# 01-Driver_Board_Overview.net
KiCad netlist of a schematic drawn in Altium Designer
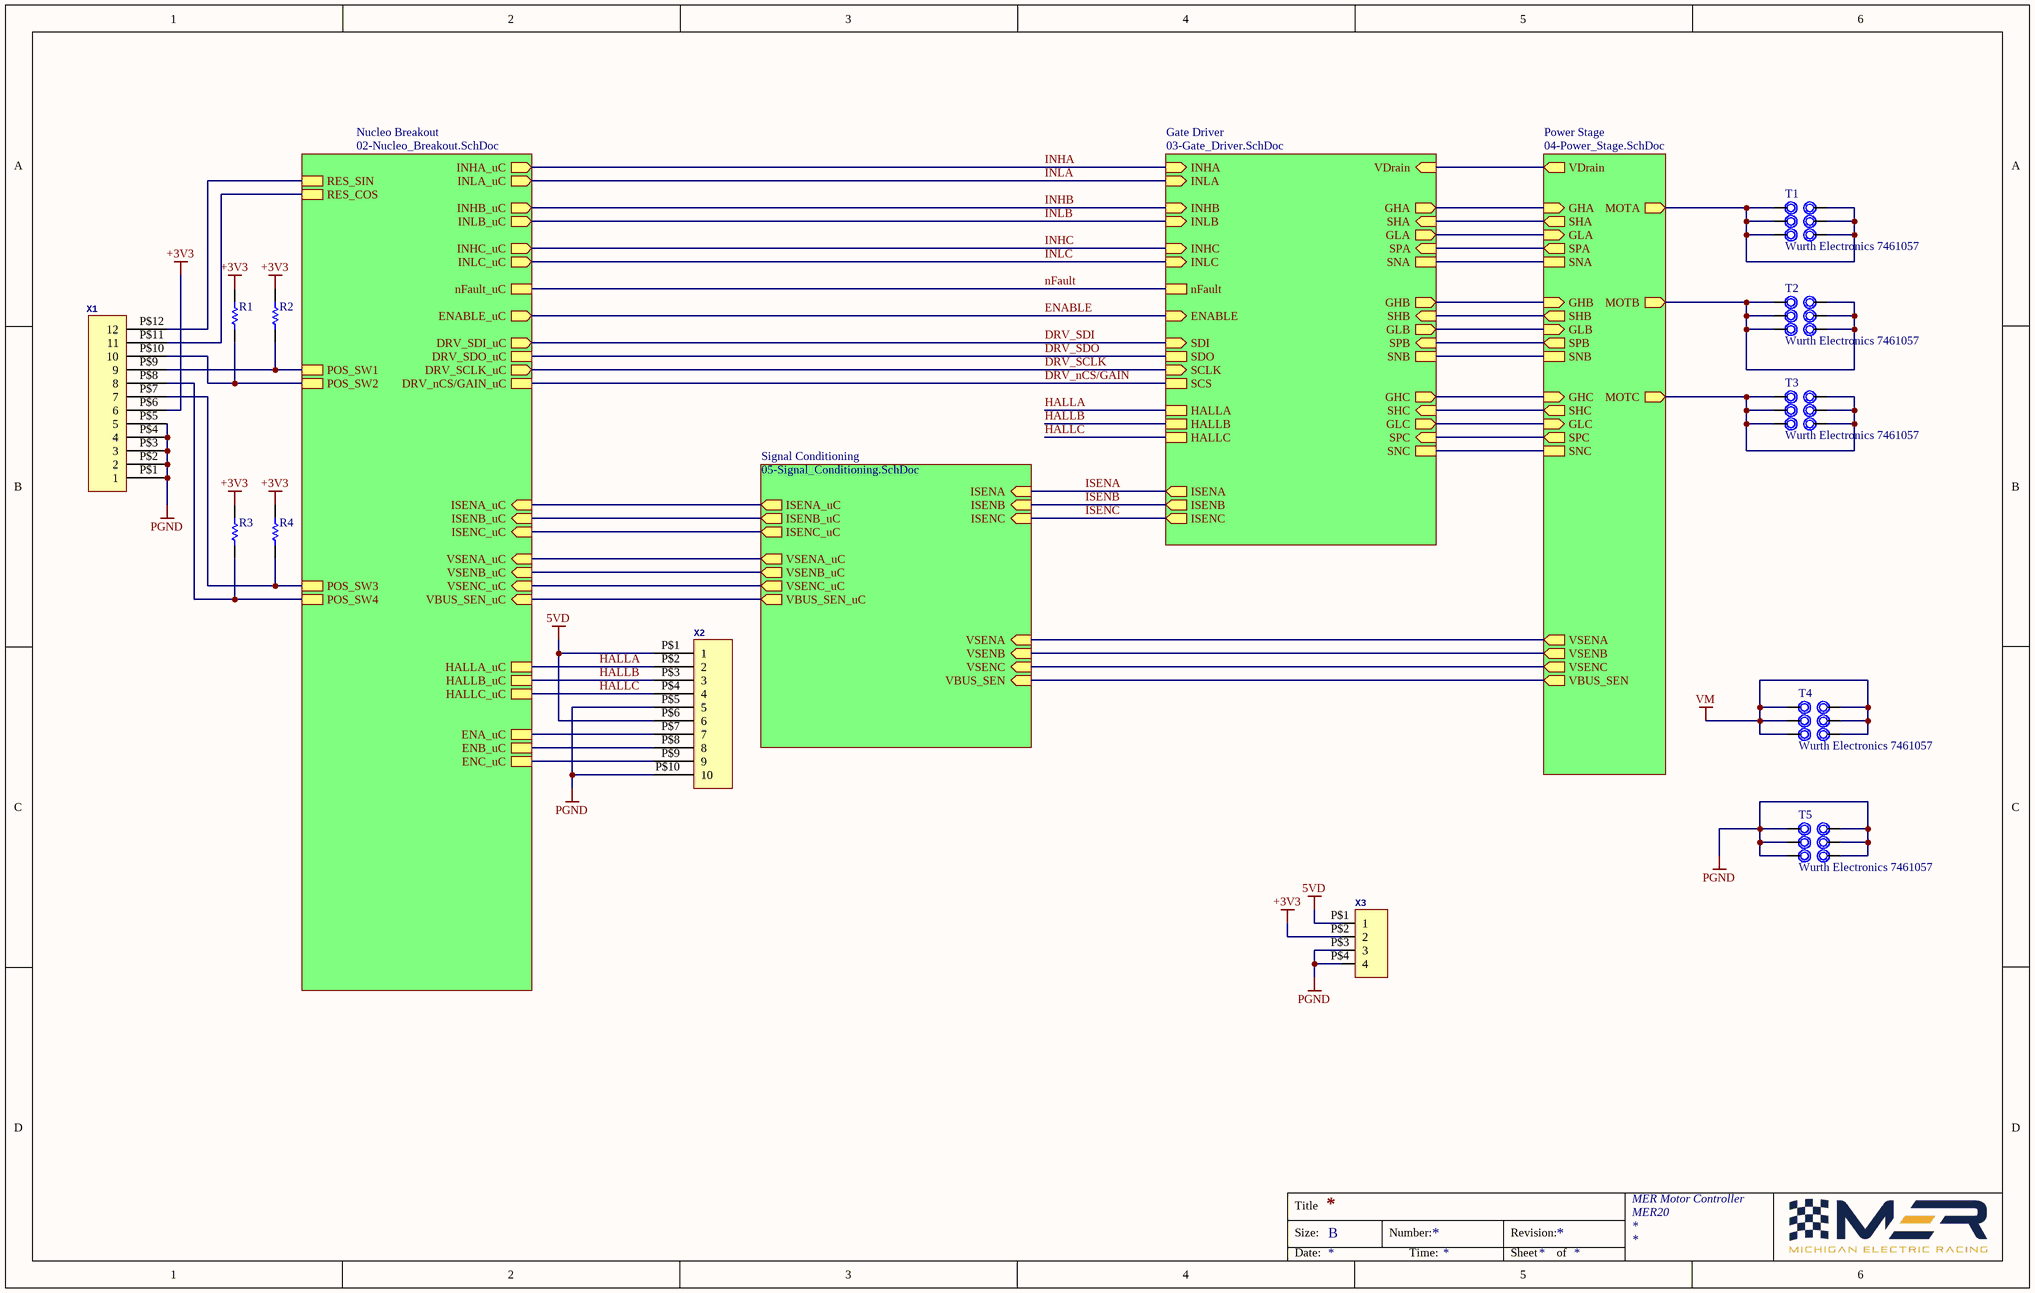
[diagram p0: 01-Driver_Board_Overview.SchDoc]

(export (version "E")
  (design (tool "Eeschema 10.0.6"))
  (components
    (comp (ref "R1")
      (value "CRCW060347K0JNEA")
      (footprint "RESC1609X50X30ML10T20")
      (fields (field (name "MANUFACTURER") "Vishay Dale"))
      (libsource (lib "Altium Content Vault") (part "RES"))
    )
    (comp (ref "R2")
      (value "CRCW060347K0JNEA")
      (footprint "RESC1609X50X30ML10T20")
      (fields (field (name "MANUFACTURER") "Vishay Dale"))
      (libsource (lib "Altium Content Vault") (part "RES"))
    )
    (comp (ref "R3")
      (value "CRCW060347K0JNEA")
      (footprint "RESC1609X50X30ML10T20")
      (fields (field (name "MANUFACTURER") "Vishay Dale"))
      (libsource (lib "Altium Content Vault") (part "RES"))
    )
    (comp (ref "R4")
      (value "CRCW060347K0JNEA")
      (footprint "RESC1609X50X30ML10T20")
      (fields (field (name "MANUFACTURER") "Vishay Dale"))
      (libsource (lib "Altium Content Vault") (part "RES"))
    )
    (comp (ref "T1")
      (value "Wurth Electronics 7461057")
      (footprint "Redcube 7461057")
      (description "Screw Terminal")
      (libsource (lib "driver_board_lib") (part "Redcube 7461057"))
    )
    (comp (ref "T2")
      (value "Wurth Electronics 7461057")
      (footprint "Redcube 7461057")
      (description "Screw Terminal")
      (libsource (lib "driver_board_lib") (part "Redcube 7461057"))
    )
    (comp (ref "T3")
      (value "Wurth Electronics 7461057")
      (footprint "Redcube 7461057")
      (description "Screw Terminal")
      (libsource (lib "driver_board_lib") (part "Redcube 7461057"))
    )
    (comp (ref "T4")
      (value "Wurth Electronics 7461057")
      (footprint "Redcube 7461057")
      (description "Screw Terminal")
      (libsource (lib "driver_board_lib") (part "Redcube 7461057"))
    )
    (comp (ref "T5")
      (value "Wurth Electronics 7461057")
      (footprint "Redcube 7461057")
      (description "Screw Terminal")
      (libsource (lib "driver_board_lib") (part "Redcube 7461057"))
    )
    (comp (ref "X1")
      (value "Molex - Micro-Fit 3.0 Series connector,  3.00mm (0.118\") pitch header, 12 positions.")
      (footprint "43045-1200")
      (libsource (lib "Molex Microfit") (part "HEADER_POS12_?43045-1200"))
    )
    (comp (ref "X2")
      (value "Molex - Micro-Fit 3.0 Series connector,  3.00mm (0.118\") pitch header, 10 positions.")
      (footprint "43045-1000")
      (libsource (lib "Molex Microfit") (part "HEADER_POS10_?43045-1000"))
    )
    (comp (ref "X3")
      (value "Molex - Micro-Fit 3.0 Series connector,  3.00mm (0.118\") pitch header, 4 positions.")
      (footprint "43045-0400")
      (libsource (lib "Molex Microfit") (part "HEADER_POS4_?43045-0401"))
    )
  )
  (nets
    (net (code "1") (name "+3V3") (class "Default")
      (node (ref "R1") (pin "2") (pinfunction "2_2") (pintype "passive"))
      (node (ref "R2") (pin "2") (pinfunction "2_2") (pintype "passive"))
      (node (ref "R3") (pin "2") (pinfunction "2_2") (pintype "passive"))
      (node (ref "R4") (pin "2") (pinfunction "2_2") (pintype "passive"))
      (node (ref "X1") (pin "P$6") (pinfunction "6_P$6") (pintype "passive"))
      (node (ref "X3") (pin "P$2") (pinfunction "2_P$2") (pintype "passive"))
    )
    (net (code "7") (name "/ENA_uC") (class "Default")
      (node (ref "X2") (pin "P$7") (pinfunction "7_P$7") (pintype "passive"))
    )
    (net (code "8") (name "/ENB_uC") (class "Default")
      (node (ref "X2") (pin "P$8") (pinfunction "8_P$8") (pintype "passive"))
    )
    (net (code "9") (name "/ENC_uC") (class "Default")
      (node (ref "X2") (pin "P$9") (pinfunction "9_P$9") (pintype "passive"))
    )
    (net (code "16") (name "/HALLA") (class "Default")
      (node (ref "X2") (pin "P$2") (pinfunction "2_P$2") (pintype "passive"))
    )
    (net (code "17") (name "/HALLB") (class "Default")
      (node (ref "X2") (pin "P$3") (pinfunction "3_P$3") (pintype "passive"))
    )
    (net (code "18") (name "/HALLC") (class "Default")
      (node (ref "X2") (pin "P$4") (pinfunction "4_P$4") (pintype "passive"))
    )
    (net (code "31") (name "/MOTA") (class "Default")
      (node (ref "T1") (pin "1") (pinfunction "1_1") (pintype "passive"))
      (node (ref "T1") (pin "2") (pinfunction "2_2") (pintype "passive"))
      (node (ref "T1") (pin "3") (pinfunction "3_3") (pintype "passive"))
      (node (ref "T1") (pin "4") (pinfunction "4_4") (pintype "passive"))
      (node (ref "T1") (pin "5") (pinfunction "5_5") (pintype "passive"))
      (node (ref "T1") (pin "6") (pinfunction "6_6") (pintype "passive"))
    )
    (net (code "32") (name "/MOTB") (class "Default")
      (node (ref "T2") (pin "1") (pinfunction "1_1") (pintype "passive"))
      (node (ref "T2") (pin "2") (pinfunction "2_2") (pintype "passive"))
      (node (ref "T2") (pin "3") (pinfunction "3_3") (pintype "passive"))
      (node (ref "T2") (pin "4") (pinfunction "4_4") (pintype "passive"))
      (node (ref "T2") (pin "5") (pinfunction "5_5") (pintype "passive"))
      (node (ref "T2") (pin "6") (pinfunction "6_6") (pintype "passive"))
    )
    (net (code "33") (name "/MOTC") (class "Default")
      (node (ref "T3") (pin "1") (pinfunction "1_1") (pintype "passive"))
      (node (ref "T3") (pin "2") (pinfunction "2_2") (pintype "passive"))
      (node (ref "T3") (pin "3") (pinfunction "3_3") (pintype "passive"))
      (node (ref "T3") (pin "4") (pinfunction "4_4") (pintype "passive"))
      (node (ref "T3") (pin "5") (pinfunction "5_5") (pintype "passive"))
      (node (ref "T3") (pin "6") (pinfunction "6_6") (pintype "passive"))
    )
    (net (code "34") (name "/POS_SW1") (class "Default")
      (node (ref "R2") (pin "1") (pinfunction "1_1") (pintype "passive"))
      (node (ref "X1") (pin "P$9") (pinfunction "9_P$9") (pintype "passive"))
    )
    (net (code "35") (name "/POS_SW2") (class "Default")
      (node (ref "R1") (pin "1") (pinfunction "1_1") (pintype "passive"))
      (node (ref "X1") (pin "P$10") (pinfunction "10_P$10") (pintype "passive"))
    )
    (net (code "36") (name "/POS_SW3") (class "Default")
      (node (ref "R4") (pin "1") (pinfunction "1_1") (pintype "passive"))
      (node (ref "X1") (pin "P$7") (pinfunction "7_P$7") (pintype "passive"))
    )
    (net (code "37") (name "/POS_SW4") (class "Default")
      (node (ref "R3") (pin "1") (pinfunction "1_1") (pintype "passive"))
      (node (ref "X1") (pin "P$8") (pinfunction "8_P$8") (pintype "passive"))
    )
    (net (code "38") (name "/RES_COS") (class "Default")
      (node (ref "X1") (pin "P$11") (pinfunction "11_P$11") (pintype "passive"))
    )
    (net (code "39") (name "/RES_SIN") (class "Default")
      (node (ref "X1") (pin "P$12") (pinfunction "12_P$12") (pintype "passive"))
    )
    (net (code "59") (name "5VD") (class "Default")
      (node (ref "X2") (pin "P$1") (pinfunction "1_P$1") (pintype "passive"))
      (node (ref "X2") (pin "P$6") (pinfunction "6_P$6") (pintype "passive"))
      (node (ref "X3") (pin "P$1") (pinfunction "1_P$1") (pintype "passive"))
    )
    (net (code "60") (name "PGND") (class "Default")
      (node (ref "T5") (pin "1") (pinfunction "1_1") (pintype "passive"))
      (node (ref "T5") (pin "2") (pinfunction "2_2") (pintype "passive"))
      (node (ref "T5") (pin "3") (pinfunction "3_3") (pintype "passive"))
      (node (ref "T5") (pin "4") (pinfunction "4_4") (pintype "passive"))
      (node (ref "T5") (pin "5") (pinfunction "5_5") (pintype "passive"))
      (node (ref "T5") (pin "6") (pinfunction "6_6") (pintype "passive"))
      (node (ref "X1") (pin "P$1") (pinfunction "1_P$1") (pintype "passive"))
      (node (ref "X1") (pin "P$2") (pinfunction "2_P$2") (pintype "passive"))
      (node (ref "X1") (pin "P$3") (pinfunction "3_P$3") (pintype "passive"))
      (node (ref "X1") (pin "P$4") (pinfunction "4_P$4") (pintype "passive"))
      (node (ref "X1") (pin "P$5") (pinfunction "5_P$5") (pintype "passive"))
      (node (ref "X2") (pin "P$10") (pinfunction "10_P$10") (pintype "passive"))
      (node (ref "X2") (pin "P$5") (pinfunction "5_P$5") (pintype "passive"))
      (node (ref "X3") (pin "P$3") (pinfunction "3_P$3") (pintype "passive"))
      (node (ref "X3") (pin "P$4") (pinfunction "4_P$4") (pintype "passive"))
    )
    (net (code "61") (name "VM") (class "Default")
      (node (ref "T4") (pin "1") (pinfunction "1_1") (pintype "passive"))
      (node (ref "T4") (pin "2") (pinfunction "2_2") (pintype "passive"))
      (node (ref "T4") (pin "3") (pinfunction "3_3") (pintype "passive"))
      (node (ref "T4") (pin "4") (pinfunction "4_4") (pintype "passive"))
      (node (ref "T4") (pin "5") (pinfunction "5_5") (pintype "passive"))
      (node (ref "T4") (pin "6") (pinfunction "6_6") (pintype "passive"))
    )
  )
)
